# OxFloodNet_sensor.net
KiCad netlist of a schematic drawn in EAGLE
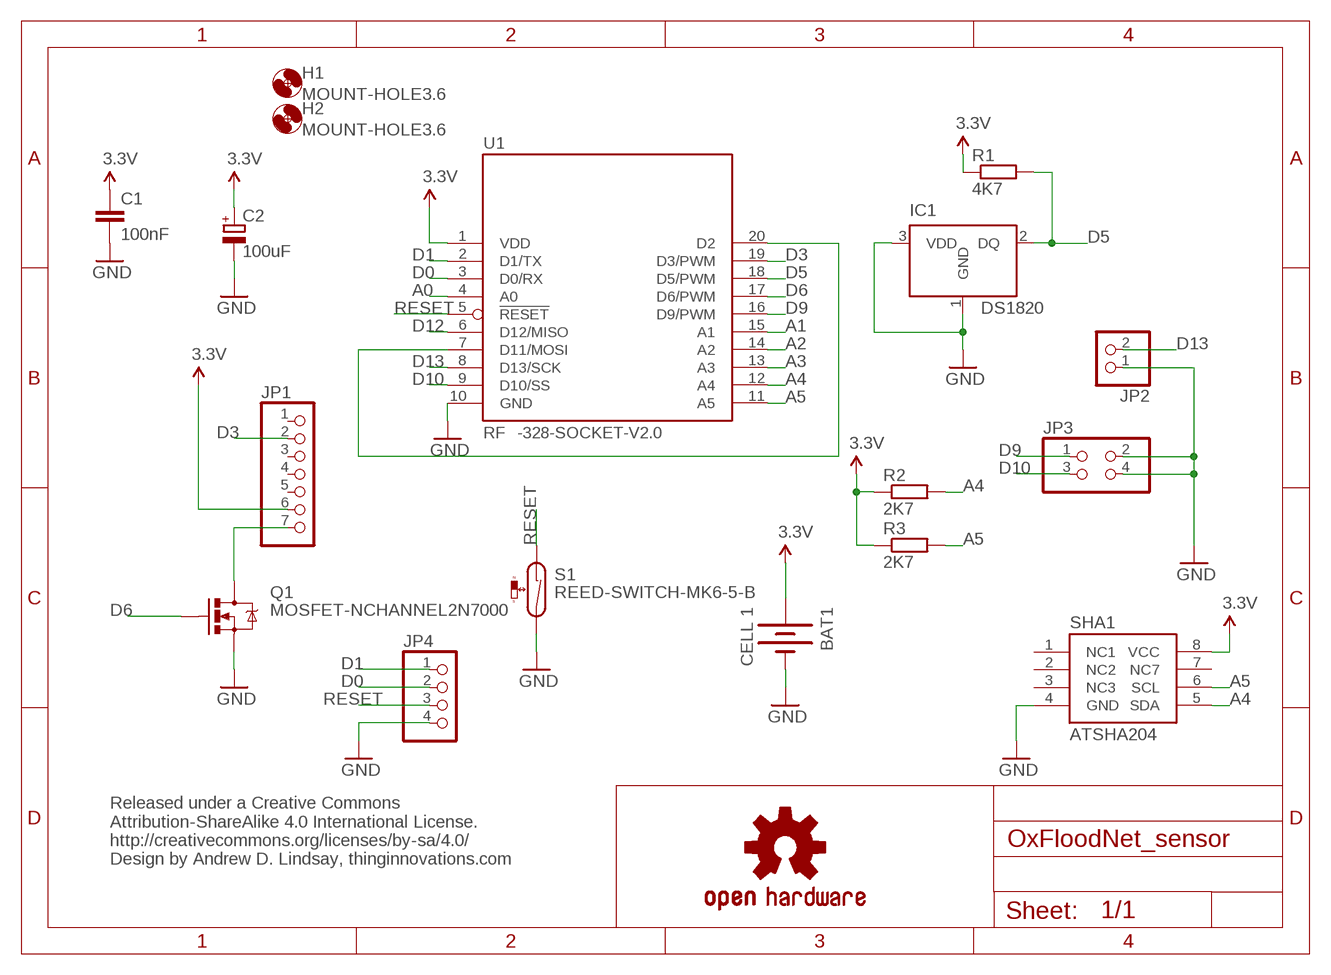
[diagram p0: schematic, sheet 1]

(export (version "E")
  (design (tool "Eeschema 10.0.6"))
  (components
    (comp (ref "BAT1")
      (value "CELL 1")
      (footprint "eagle-import:BATTERY-AA")
      (libsource (lib "eagle-import") (part "BATTERYAA"))
    )
    (comp (ref "C1")
      (value "100nF")
      (footprint "eagle-import:C025-024X044")
      (libsource (lib "eagle-import") (part "C-EU025-024X044"))
    )
    (comp (ref "C2")
      (value "100uF")
      (footprint "eagle-import:E2,5-6E")
      (libsource (lib "eagle-import") (part "CPOL-EUE2,5-6E"))
    )
    (comp (ref "H1")
      (value "MOUNT-HOLE3.6")
      (footprint "eagle-import:3,6")
      (libsource (lib "eagle-import") (part "MOUNT-HOLE3.6"))
    )
    (comp (ref "H2")
      (value "MOUNT-HOLE3.6")
      (footprint "eagle-import:3,6")
      (libsource (lib "eagle-import") (part "MOUNT-HOLE3.6"))
    )
    (comp (ref "IC1")
      (value "DS1820")
      (footprint "eagle-import:TO-92")
      (libsource (lib "eagle-import") (part "DS1820"))
    )
    (comp (ref "JP1")
      (value "1X07")
      (footprint "eagle-import:1X07")
      (libsource (lib "eagle-import") (part "1X07"))
    )
    (comp (ref "JP2")
      (value "1X02")
      (footprint "eagle-import:1X02")
      (libsource (lib "eagle-import") (part "1X02"))
    )
    (comp (ref "JP3")
      (value "2X02")
      (footprint "eagle-import:2X02")
      (libsource (lib "eagle-import") (part "2X02"))
    )
    (comp (ref "JP4")
      (value "PINHD-1X4")
      (footprint "eagle-import:1X04")
      (libsource (lib "eagle-import") (part "PINHD-1X4"))
    )
    (comp (ref "LOGO1")
      (value "OSHW-LOGOM")
      (footprint "eagle-import:OSHW-LOGO-M")
      (libsource (lib "eagle-import") (part "OSHW-LOGOM"))
    )
    (comp (ref "Q1")
      (value "MOSFET-NCHANNEL2N7000")
      (footprint "eagle-import:TO-92")
      (libsource (lib "eagle-import") (part "MOSFET-NCHANNEL2N7000"))
    )
    (comp (ref "R1")
      (value "4K7")
      (footprint "eagle-import:0207_7")
      (libsource (lib "eagle-import") (part "R-EU_0207/7"))
    )
    (comp (ref "R2")
      (value "2K7")
      (footprint "eagle-import:0207_7")
      (libsource (lib "eagle-import") (part "R-EU_0207/7"))
    )
    (comp (ref "R3")
      (value "2K7")
      (footprint "eagle-import:0207_7")
      (libsource (lib "eagle-import") (part "R-EU_0207/7"))
    )
    (comp (ref "S1")
      (value "REED-SWITCH-MK6-5-B")
      (footprint "eagle-import:MK6-5")
      (fields (field (name "MF") "MEDER") (field (name "MPN") "MK6-5-B"))
      (libsource (lib "eagle-import") (part "REED-SWITCH-MK6-5-B"))
    )
    (comp (ref "SHA1")
      (value "ATSHA204")
      (footprint "eagle-import:SOIC8")
      (libsource (lib "eagle-import") (part "ATSHA204"))
    )
    (comp (ref "U1")
      (value "RF�-328-SOCKET-V2.0")
      (footprint "eagle-import:RF�-SOCKET-V2.0")
      (libsource (lib "eagle-import") (part "RF�-328-SOCKET-V2.0"))
    )
  )
  (nets
    (net (code "1") (name "/A0") (class "Default")
      (node (ref "U1") (pin "4") (pinfunction "A0_4") (pintype "bidirectional"))
    )
    (net (code "2") (name "/A1") (class "Default")
      (node (ref "U1") (pin "15") (pinfunction "A1_15") (pintype "bidirectional"))
    )
    (net (code "3") (name "/A2") (class "Default")
      (node (ref "U1") (pin "14") (pinfunction "A2_14") (pintype "bidirectional"))
    )
    (net (code "4") (name "/A3") (class "Default")
      (node (ref "U1") (pin "13") (pinfunction "A3_13") (pintype "bidirectional"))
    )
    (net (code "5") (name "/A4") (class "Default")
      (node (ref "R2") (pin "2") (pinfunction "2_2") (pintype "passive"))
      (node (ref "SHA1") (pin "5") (pinfunction "SDA_5") (pintype "bidirectional"))
      (node (ref "U1") (pin "12") (pinfunction "A4_12") (pintype "output"))
    )
    (net (code "6") (name "/A5") (class "Default")
      (node (ref "R3") (pin "2") (pinfunction "2_2") (pintype "passive"))
      (node (ref "SHA1") (pin "6") (pinfunction "SCL_6") (pintype "bidirectional"))
      (node (ref "U1") (pin "11") (pinfunction "A5_11") (pintype "bidirectional"))
    )
    (net (code "7") (name "/D0") (class "Default")
      (node (ref "JP4") (pin "2") (pinfunction "2_2") (pintype "passive"))
      (node (ref "U1") (pin "3") (pinfunction "D0/RX_3") (pintype "input"))
    )
    (net (code "8") (name "/D1") (class "Default")
      (node (ref "JP4") (pin "1") (pinfunction "1_1") (pintype "passive"))
      (node (ref "U1") (pin "2") (pinfunction "D1/TX_2") (pintype "output"))
    )
    (net (code "9") (name "/D3") (class "Default")
      (node (ref "JP1") (pin "2") (pinfunction "2_2") (pintype "passive"))
      (node (ref "U1") (pin "19") (pinfunction "D3/PWM_19") (pintype "bidirectional"))
    )
    (net (code "10") (name "/D5") (class "Default")
      (node (ref "IC1") (pin "2") (pinfunction "DQ_2") (pintype "output"))
      (node (ref "R1") (pin "2") (pinfunction "2_2") (pintype "passive"))
      (node (ref "U1") (pin "18") (pinfunction "D5/PWM_18") (pintype "bidirectional"))
    )
    (net (code "11") (name "/D6") (class "Default")
      (node (ref "Q1") (pin "2") (pinfunction "G_2") (pintype "passive"))
      (node (ref "U1") (pin "17") (pinfunction "D6/PWM_17") (pintype "bidirectional"))
    )
    (net (code "12") (name "/D9") (class "Default")
      (node (ref "JP3") (pin "1") (pinfunction "1_1") (pintype "passive"))
      (node (ref "U1") (pin "16") (pinfunction "D9/PWM_16") (pintype "input"))
    )
    (net (code "13") (name "/D10") (class "Default")
      (node (ref "JP3") (pin "3") (pinfunction "3_3") (pintype "passive"))
      (node (ref "U1") (pin "9") (pinfunction "D10/SS_9") (pintype "bidirectional"))
    )
    (net (code "14") (name "/D12") (class "Default")
      (node (ref "U1") (pin "6") (pinfunction "D12/MISO_6") (pintype "bidirectional"))
    )
    (net (code "15") (name "/D13") (class "Default")
      (node (ref "JP2") (pin "2") (pinfunction "2_2") (pintype "passive"))
      (node (ref "U1") (pin "8") (pinfunction "D13/SCK_8") (pintype "bidirectional"))
    )
    (net (code "16") (name "/RESET") (class "Default")
      (node (ref "JP4") (pin "3") (pinfunction "3_3") (pintype "passive"))
      (node (ref "S1") (pin "1") (pinfunction "1_1") (pintype "passive"))
      (node (ref "U1") (pin "5") (pinfunction "~{RESET}_5") (pintype "input"))
    )
    (net (code "17") (name "3.3V") (class "Default")
      (node (ref "BAT1") (pin "PWR@1") (pinfunction "+_PWR@1") (pintype "power_in"))
      (node (ref "C1") (pin "1") (pinfunction "1_1") (pintype "passive"))
      (node (ref "C2") (pin "+") (pinfunction "+_+") (pintype "passive"))
      (node (ref "JP1") (pin "6") (pinfunction "6_6") (pintype "passive"))
      (node (ref "R1") (pin "1") (pinfunction "1_1") (pintype "passive"))
      (node (ref "R2") (pin "1") (pinfunction "1_1") (pintype "passive"))
      (node (ref "R3") (pin "1") (pinfunction "1_1") (pintype "passive"))
      (node (ref "SHA1") (pin "8") (pinfunction "VCC_8") (pintype "power_in"))
      (node (ref "U1") (pin "1") (pinfunction "VDD_1") (pintype "power_in"))
    )
    (net (code "18") (name "GND") (class "Default")
      (node (ref "BAT1") (pin "GND@1") (pinfunction "-_GND@1") (pintype "power_in"))
      (node (ref "C1") (pin "2") (pinfunction "2_2") (pintype "passive"))
      (node (ref "C2") (pin "-") (pinfunction "-_-") (pintype "passive"))
      (node (ref "IC1") (pin "1") (pinfunction "GND_1") (pintype "power_in"))
      (node (ref "IC1") (pin "3") (pinfunction "VDD_3") (pintype "input"))
      (node (ref "JP2") (pin "1") (pinfunction "1_1") (pintype "passive"))
      (node (ref "JP3") (pin "2") (pinfunction "2_2") (pintype "passive"))
      (node (ref "JP3") (pin "4") (pinfunction "4_4") (pintype "passive"))
      (node (ref "JP4") (pin "4") (pinfunction "4_4") (pintype "passive"))
      (node (ref "Q1") (pin "1") (pinfunction "S_1") (pintype "passive"))
      (node (ref "S1") (pin "2") (pinfunction "2_2") (pintype "passive"))
      (node (ref "SHA1") (pin "4") (pinfunction "GND_4") (pintype "power_in"))
      (node (ref "U1") (pin "10") (pinfunction "GND_10") (pintype "power_in"))
    )
    (net (code "19") (name "Net-(Q1-D)") (class "Default")
      (node (ref "JP1") (pin "7") (pinfunction "7_7") (pintype "passive"))
      (node (ref "Q1") (pin "3") (pinfunction "D_3") (pintype "passive"))
    )
    (net (code "20") (name "Net-(U1-D11{slash}MOSI)") (class "Default")
      (node (ref "U1") (pin "20") (pinfunction "D2_20") (pintype "bidirectional"))
      (node (ref "U1") (pin "7") (pinfunction "D11/MOSI_7") (pintype "bidirectional"))
    )
    (net (code "21") (name "unconnected-(JP1-Pad1)") (class "Default")
      (node (ref "JP1") (pin "1") (pinfunction "1_1") (pintype "passive"))
    )
    (net (code "22") (name "unconnected-(JP1-Pad3)") (class "Default")
      (node (ref "JP1") (pin "3") (pinfunction "3_3") (pintype "passive"))
    )
    (net (code "23") (name "unconnected-(JP1-Pad4)") (class "Default")
      (node (ref "JP1") (pin "4") (pinfunction "4_4") (pintype "passive"))
    )
    (net (code "24") (name "unconnected-(JP1-Pad5)") (class "Default")
      (node (ref "JP1") (pin "5") (pinfunction "5_5") (pintype "passive"))
    )
    (net (code "25") (name "unconnected-(SHA1-NC1-Pad1)") (class "Default")
      (node (ref "SHA1") (pin "1") (pinfunction "NC1_1") (pintype "no_connect"))
    )
    (net (code "26") (name "unconnected-(SHA1-NC2-Pad2)") (class "Default")
      (node (ref "SHA1") (pin "2") (pinfunction "NC2_2") (pintype "no_connect"))
    )
    (net (code "27") (name "unconnected-(SHA1-NC3-Pad3)") (class "Default")
      (node (ref "SHA1") (pin "3") (pinfunction "NC3_3") (pintype "no_connect"))
    )
    (net (code "28") (name "unconnected-(SHA1-NC7-Pad7)") (class "Default")
      (node (ref "SHA1") (pin "7") (pinfunction "NC7_7") (pintype "no_connect"))
    )
  )
)
